# LPCB220_-_PUSHER_INTERLOCK.net
KiCad netlist of a schematic drawn in Altium Designer
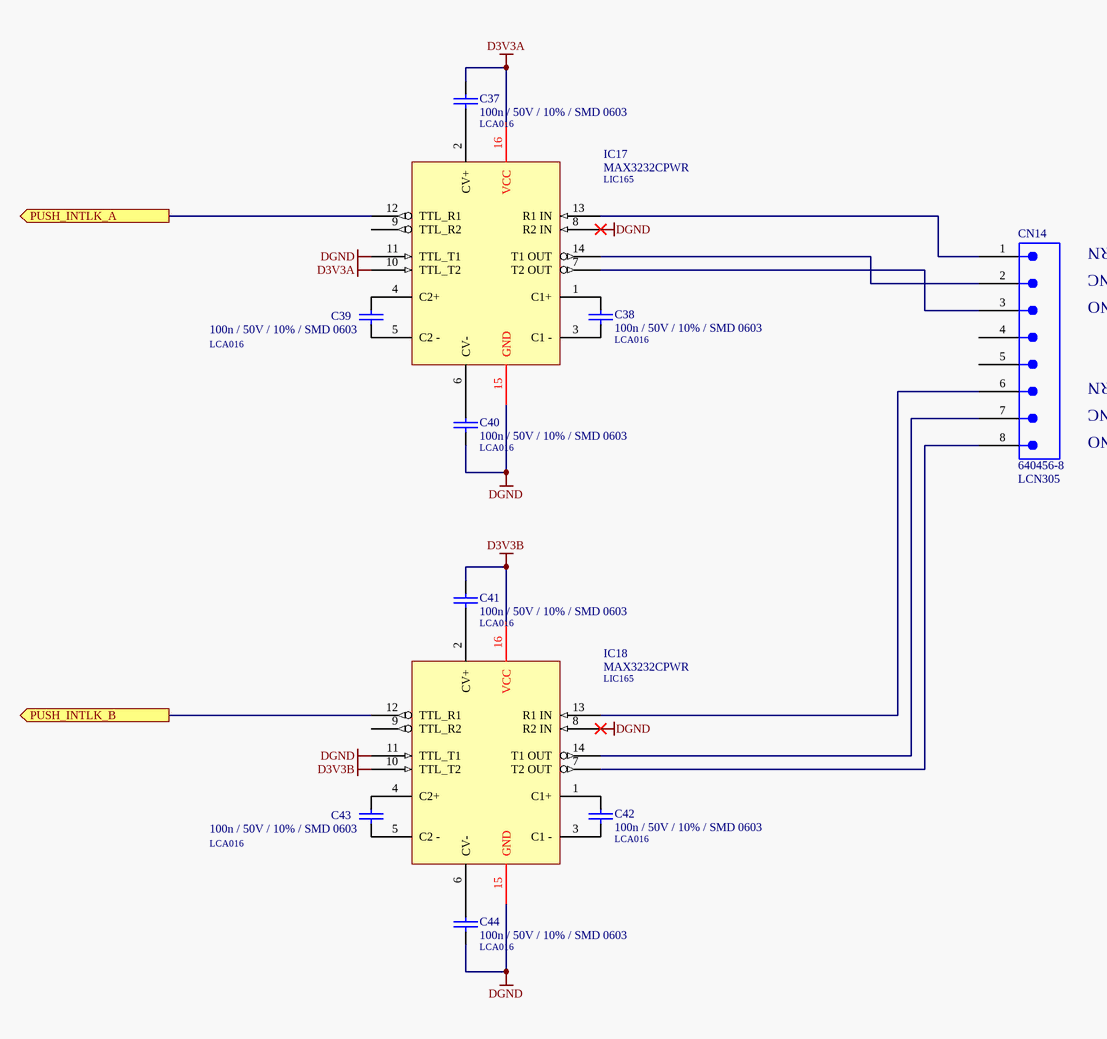
[diagram p0: LPCB220 - PUSHER INTERLOCK.SchDoc]

(export (version "E")
  (design (tool "Eeschema 10.0.6"))
  (components
    (comp (ref "C37")
      (value "100n / 50V / 10% / SMD 0603")
      (footprint "LFP011__CC1608-0603-IPC7351_B")
      (description "Capacitor, Ceramic Chip, 100nF, 50V, 10%, SMD 0603")
      (fields (field (name "LDL_NUMBER") "LCA016"))
      (libsource (lib "LDL_Capacitors") (part "100n / 50V / 10% / SMD 0603"))
    )
    (comp (ref "C38")
      (value "100n / 50V / 10% / SMD 0603")
      (footprint "LFP011__CC1608-0603-IPC7351_B")
      (description "Capacitor, Ceramic Chip, 100nF, 50V, 10%, SMD 0603")
      (fields (field (name "LDL_NUMBER") "LCA016"))
      (libsource (lib "LDL_Capacitors") (part "100n / 50V / 10% / SMD 0603"))
    )
    (comp (ref "C39")
      (value "100n / 50V / 10% / SMD 0603")
      (footprint "LFP011__CC1608-0603-IPC7351_B")
      (description "Capacitor, Ceramic Chip, 100nF, 50V, 10%, SMD 0603")
      (fields (field (name "LDL_NUMBER") "LCA016"))
      (libsource (lib "LDL_Capacitors") (part "100n / 50V / 10% / SMD 0603"))
    )
    (comp (ref "C40")
      (value "100n / 50V / 10% / SMD 0603")
      (footprint "LFP011__CC1608-0603-IPC7351_B")
      (description "Capacitor, Ceramic Chip, 100nF, 50V, 10%, SMD 0603")
      (fields (field (name "LDL_NUMBER") "LCA016"))
      (libsource (lib "LDL_Capacitors") (part "100n / 50V / 10% / SMD 0603"))
    )
    (comp (ref "C41")
      (value "100n / 50V / 10% / SMD 0603")
      (footprint "LFP011__CC1608-0603-IPC7351_B")
      (description "Capacitor, Ceramic Chip, 100nF, 50V, 10%, SMD 0603")
      (fields (field (name "LDL_NUMBER") "LCA016"))
      (libsource (lib "LDL_Capacitors") (part "100n / 50V / 10% / SMD 0603"))
    )
    (comp (ref "C42")
      (value "100n / 50V / 10% / SMD 0603")
      (footprint "LFP011__CC1608-0603-IPC7351_B")
      (description "Capacitor, Ceramic Chip, 100nF, 50V, 10%, SMD 0603")
      (fields (field (name "LDL_NUMBER") "LCA016"))
      (libsource (lib "LDL_Capacitors") (part "100n / 50V / 10% / SMD 0603"))
    )
    (comp (ref "C43")
      (value "100n / 50V / 10% / SMD 0603")
      (footprint "LFP011__CC1608-0603-IPC7351_B")
      (description "Capacitor, Ceramic Chip, 100nF, 50V, 10%, SMD 0603")
      (fields (field (name "LDL_NUMBER") "LCA016"))
      (libsource (lib "LDL_Capacitors") (part "100n / 50V / 10% / SMD 0603"))
    )
    (comp (ref "C44")
      (value "100n / 50V / 10% / SMD 0603")
      (footprint "LFP011__CC1608-0603-IPC7351_B")
      (description "Capacitor, Ceramic Chip, 100nF, 50V, 10%, SMD 0603")
      (fields (field (name "LDL_NUMBER") "LCA016"))
      (libsource (lib "LDL_Capacitors") (part "100n / 50V / 10% / SMD 0603"))
    )
    (comp (ref "CN14")
      (value "640456-8")
      (footprint "640456-8")
      (description "Connector, Male Header, 8 Way")
      (fields (field (name "LDL_NUMBER") "LCN305"))
      (libsource (lib "LDL_Connectors") (part "640456-8"))
    )
    (comp (ref "IC17")
      (value "MAX3232CPWR")
      (footprint "LFP049__TSSOP-16")
      (description "IC, RS232 Line Driver, 3.3V, SMD TSSOP16")
      (fields (field (name "LDL_NUMBER") "LIC165"))
      (libsource (lib "LDL_Semiconductors") (part "MAX3232CPWR"))
    )
    (comp (ref "IC18")
      (value "MAX3232CPWR")
      (footprint "LFP049__TSSOP-16")
      (description "IC, RS232 Line Driver, 3.3V, SMD TSSOP16")
      (fields (field (name "LDL_NUMBER") "LIC165"))
      (libsource (lib "LDL_Semiconductors") (part "MAX3232CPWR"))
    )
  )
  (nets
    (net (code "1") (name "/PUSH_INTLK_A") (class "Default")
      (node (ref "IC17") (pin "12") (pinfunction "TTL_R1_12") (pintype "output"))
    )
    (net (code "2") (name "/PUSH_INTLK_B") (class "Default")
      (node (ref "IC18") (pin "12") (pinfunction "TTL_R1_12") (pintype "output"))
    )
    (net (code "3") (name "D3V3A") (class "Default")
      (node (ref "C37") (pin "1") (pintype "passive"))
      (node (ref "IC17") (pin "10") (pinfunction "TTL_T2_10") (pintype "input"))
      (node (ref "IC17") (pin "16") (pinfunction "VCC_16") (pintype "power_in"))
    )
    (net (code "4") (name "D3V3B") (class "Default")
      (node (ref "C41") (pin "1") (pintype "passive"))
      (node (ref "IC18") (pin "10") (pinfunction "TTL_T2_10") (pintype "input"))
      (node (ref "IC18") (pin "16") (pinfunction "VCC_16") (pintype "power_in"))
    )
    (net (code "5") (name "DGND") (class "Default")
      (node (ref "C40") (pin "2") (pintype "passive"))
      (node (ref "C44") (pin "2") (pintype "passive"))
      (node (ref "IC17") (pin "11") (pinfunction "TTL_T1_11") (pintype "input"))
      (node (ref "IC17") (pin "15") (pinfunction "GND_15") (pintype "power_in"))
      (node (ref "IC17") (pin "8") (pinfunction "R2_IN_8") (pintype "input"))
      (node (ref "IC18") (pin "11") (pinfunction "TTL_T1_11") (pintype "input"))
      (node (ref "IC18") (pin "15") (pinfunction "GND_15") (pintype "power_in"))
      (node (ref "IC18") (pin "8") (pinfunction "R2_IN_8") (pintype "input"))
    )
    (net (code "6") (name "Net-(IC17-C1+)") (class "Default")
      (node (ref "C38") (pin "1") (pintype "passive"))
      (node (ref "IC17") (pin "1") (pinfunction "C1+_1") (pintype "passive"))
    )
    (net (code "7") (name "Net-(IC17-C1_-)") (class "Default")
      (node (ref "C38") (pin "2") (pintype "passive"))
      (node (ref "IC17") (pin "3") (pinfunction "C1_-_3") (pintype "passive"))
    )
    (net (code "8") (name "Net-(IC17-C2+)") (class "Default")
      (node (ref "C39") (pin "1") (pintype "passive"))
      (node (ref "IC17") (pin "4") (pinfunction "C2+_4") (pintype "passive"))
    )
    (net (code "9") (name "Net-(IC17-C2_-)") (class "Default")
      (node (ref "C39") (pin "2") (pintype "passive"))
      (node (ref "IC17") (pin "5") (pinfunction "C2_-_5") (pintype "passive"))
    )
    (net (code "10") (name "Net-(IC17-CV+)") (class "Default")
      (node (ref "C37") (pin "2") (pintype "passive"))
      (node (ref "IC17") (pin "2") (pinfunction "CV+_2") (pintype "passive"))
    )
    (net (code "11") (name "Net-(IC17-CV-)") (class "Default")
      (node (ref "C40") (pin "1") (pintype "passive"))
      (node (ref "IC17") (pin "6") (pinfunction "CV-_6") (pintype "passive"))
    )
    (net (code "12") (name "Net-(IC17-R1_IN)") (class "Default")
      (node (ref "CN14") (pin "1") (pinfunction "1_1") (pintype "passive"))
      (node (ref "IC17") (pin "13") (pinfunction "R1_IN_13") (pintype "input"))
    )
    (net (code "13") (name "Net-(IC17-T1_OUT)") (class "Default")
      (node (ref "CN14") (pin "2") (pinfunction "2_2") (pintype "passive"))
      (node (ref "IC17") (pin "14") (pinfunction "T1_OUT_14") (pintype "output"))
    )
    (net (code "14") (name "Net-(IC17-T2_OUT)") (class "Default")
      (node (ref "CN14") (pin "3") (pinfunction "3_3") (pintype "passive"))
      (node (ref "IC17") (pin "7") (pinfunction "T2_OUT_7") (pintype "output"))
    )
    (net (code "15") (name "Net-(IC18-C1+)") (class "Default")
      (node (ref "C42") (pin "1") (pintype "passive"))
      (node (ref "IC18") (pin "1") (pinfunction "C1+_1") (pintype "passive"))
    )
    (net (code "16") (name "Net-(IC18-C1_-)") (class "Default")
      (node (ref "C42") (pin "2") (pintype "passive"))
      (node (ref "IC18") (pin "3") (pinfunction "C1_-_3") (pintype "passive"))
    )
    (net (code "17") (name "Net-(IC18-C2+)") (class "Default")
      (node (ref "C43") (pin "1") (pintype "passive"))
      (node (ref "IC18") (pin "4") (pinfunction "C2+_4") (pintype "passive"))
    )
    (net (code "18") (name "Net-(IC18-C2_-)") (class "Default")
      (node (ref "C43") (pin "2") (pintype "passive"))
      (node (ref "IC18") (pin "5") (pinfunction "C2_-_5") (pintype "passive"))
    )
    (net (code "19") (name "Net-(IC18-CV+)") (class "Default")
      (node (ref "C41") (pin "2") (pintype "passive"))
      (node (ref "IC18") (pin "2") (pinfunction "CV+_2") (pintype "passive"))
    )
    (net (code "20") (name "Net-(IC18-CV-)") (class "Default")
      (node (ref "C44") (pin "1") (pintype "passive"))
      (node (ref "IC18") (pin "6") (pinfunction "CV-_6") (pintype "passive"))
    )
    (net (code "21") (name "Net-(IC18-R1_IN)") (class "Default")
      (node (ref "CN14") (pin "6") (pinfunction "6_6") (pintype "passive"))
      (node (ref "IC18") (pin "13") (pinfunction "R1_IN_13") (pintype "input"))
    )
    (net (code "22") (name "Net-(IC18-T1_OUT)") (class "Default")
      (node (ref "CN14") (pin "7") (pinfunction "7_7") (pintype "passive"))
      (node (ref "IC18") (pin "14") (pinfunction "T1_OUT_14") (pintype "output"))
    )
    (net (code "23") (name "Net-(IC18-T2_OUT)") (class "Default")
      (node (ref "CN14") (pin "8") (pinfunction "8_8") (pintype "passive"))
      (node (ref "IC18") (pin "7") (pinfunction "T2_OUT_7") (pintype "output"))
    )
    (net (code "24") (name "unconnected-(CN14-Pad4)") (class "Default")
      (node (ref "CN14") (pin "4") (pinfunction "4_4") (pintype "passive"))
    )
    (net (code "25") (name "unconnected-(CN14-Pad5)") (class "Default")
      (node (ref "CN14") (pin "5") (pinfunction "5_5") (pintype "passive"))
    )
    (net (code "26") (name "unconnected-(IC17-TTL_R2-Pad9)") (class "Default")
      (node (ref "IC17") (pin "9") (pinfunction "TTL_R2_9") (pintype "output"))
    )
    (net (code "27") (name "unconnected-(IC18-TTL_R2-Pad9)") (class "Default")
      (node (ref "IC18") (pin "9") (pinfunction "TTL_R2_9") (pintype "output"))
    )
  )
)
